# proteccionBat.net
KiCad netlist of a schematic drawn in Altium Designer
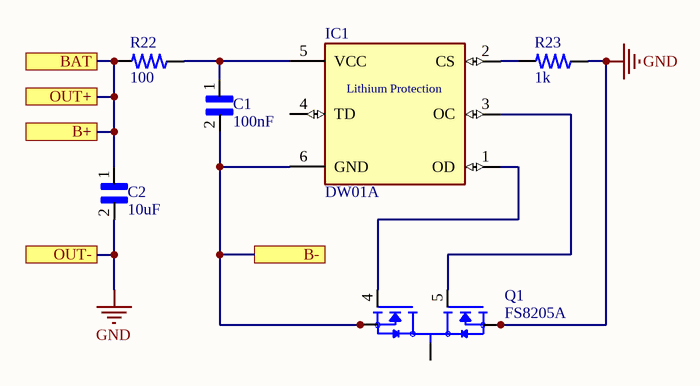
[diagram p0: proteccionBat.SchDoc]

(export (version "E")
  (design (tool "Eeschema 10.0.6"))
  (components
    (comp (ref "C1")
      (value "100nF")
      (footprint "CAPC1608X87N")
      (description "Cap, Mlcc, X7r, 1uf, 16v, 0603")
      (fields (field (name "MF") "Multicomp") (field (name "MP") "MC0603B105K160CT"))
      (libsource (lib "cap0603") (part "MC0603B105K160CT"))
    )
    (comp (ref "C2")
      (value "10uF")
      (footprint "CAPC1608X87N")
      (description "Cap, Mlcc, X7r, 1uf, 16v, 0603")
      (fields (field (name "MF") "Multicomp") (field (name "MP") "MC0603B105K160CT"))
      (libsource (lib "cap0603") (part "MC0603B105K160CT"))
    )
    (comp (ref "IC1")
      (value "DW01A")
      (footprint "SOT23-6")
      (description "Pushbutton Switch SPST-NC Standard Panel Mount, Front")
      (fields (field (name "MF") "Fortune Semiconductor"))
      (libsource (lib "DW01A") (part "DW01A"))
    )
    (comp (ref "Q1")
      (value "FS8205A")
      (footprint "SOP65P640X120-8N")
      (fields (field (name "MF") "Fortune Semiconductor"))
      (libsource (lib "FS8285A") (part "FS8205A"))
    )
    (comp (ref "R22")
      (value "100")
      (footprint "RESC1608X50N")
      (description "Res, Thin Film, 13r, 0.1%, 0.1w, 0603")
      (fields (field (name "MP") "RP73D1J13RBTDG") (field (name "MF") "TE Connectivity"))
      (libsource (lib "Res0603") (part "RP73D1J13RBTDG"))
    )
    (comp (ref "R23")
      (value "1k")
      (footprint "RESC1608X50N")
      (description "Res, Thin Film, 13r, 0.1%, 0.1w, 0603")
      (fields (field (name "MP") "RP73D1J13RBTDG") (field (name "MF") "TE Connectivity"))
      (libsource (lib "Res0603") (part "RP73D1J13RBTDG"))
    )
  )
  (nets
    (net (code "1") (name "/B+") (class "Default")
      (node (ref "C2") (pin "1") (pinfunction "1_1") (pintype "passive"))
      (node (ref "R22") (pin "2") (pinfunction "2_2") (pintype "passive"))
    )
    (net (code "2") (name "/B-") (class "Default")
      (node (ref "C1") (pin "2") (pinfunction "2_2") (pintype "passive"))
      (node (ref "IC1") (pin "6") (pinfunction "GND_6") (pintype "power_in"))
      (node (ref "Q1") (pin "2") (pinfunction "S1_2") (pintype "passive"))
      (node (ref "Q1") (pin "3") (pinfunction "S1_3") (pintype "passive"))
    )
    (net (code "3") (name "GND") (class "Default")
      (node (ref "C2") (pin "2") (pinfunction "2_2") (pintype "passive"))
      (node (ref "Q1") (pin "6") (pinfunction "S2_6") (pintype "passive"))
      (node (ref "Q1") (pin "7") (pinfunction "S2_7") (pintype "passive"))
      (node (ref "R23") (pin "1") (pinfunction "1_1") (pintype "passive"))
    )
    (net (code "4") (name "Net-(IC1-CS)") (class "Default")
      (node (ref "IC1") (pin "2") (pinfunction "CS_2") (pintype "bidirectional"))
      (node (ref "R23") (pin "2") (pinfunction "2_2") (pintype "passive"))
    )
    (net (code "5") (name "Net-(IC1-OC)") (class "Default")
      (node (ref "IC1") (pin "3") (pinfunction "OC_3") (pintype "bidirectional"))
      (node (ref "Q1") (pin "5") (pinfunction "G2_5") (pintype "passive"))
    )
    (net (code "6") (name "Net-(IC1-OD)") (class "Default")
      (node (ref "IC1") (pin "1") (pinfunction "OD_1") (pintype "bidirectional"))
      (node (ref "Q1") (pin "4") (pinfunction "G1_4") (pintype "passive"))
    )
    (net (code "7") (name "Net-(IC1-VCC)") (class "Default")
      (node (ref "C1") (pin "1") (pinfunction "1_1") (pintype "passive"))
      (node (ref "IC1") (pin "5") (pinfunction "VCC_5") (pintype "power_in"))
      (node (ref "R22") (pin "1") (pinfunction "1_1") (pintype "passive"))
    )
    (net (code "8") (name "Net-(Q1-D12-Pad1)") (class "Default")
      (node (ref "Q1") (pin "1") (pinfunction "D12_1") (pintype "passive"))
      (node (ref "Q1") (pin "8") (pinfunction "D12_8") (pintype "passive"))
    )
    (net (code "9") (name "unconnected-(IC1-TD-Pad4)") (class "Default")
      (node (ref "IC1") (pin "4") (pinfunction "TD_4") (pintype "bidirectional"))
    )
  )
)
